# SCH_PoC_draadloze_communicatie_Jao.net
KiCad netlist of a schematic drawn in EasyEDA
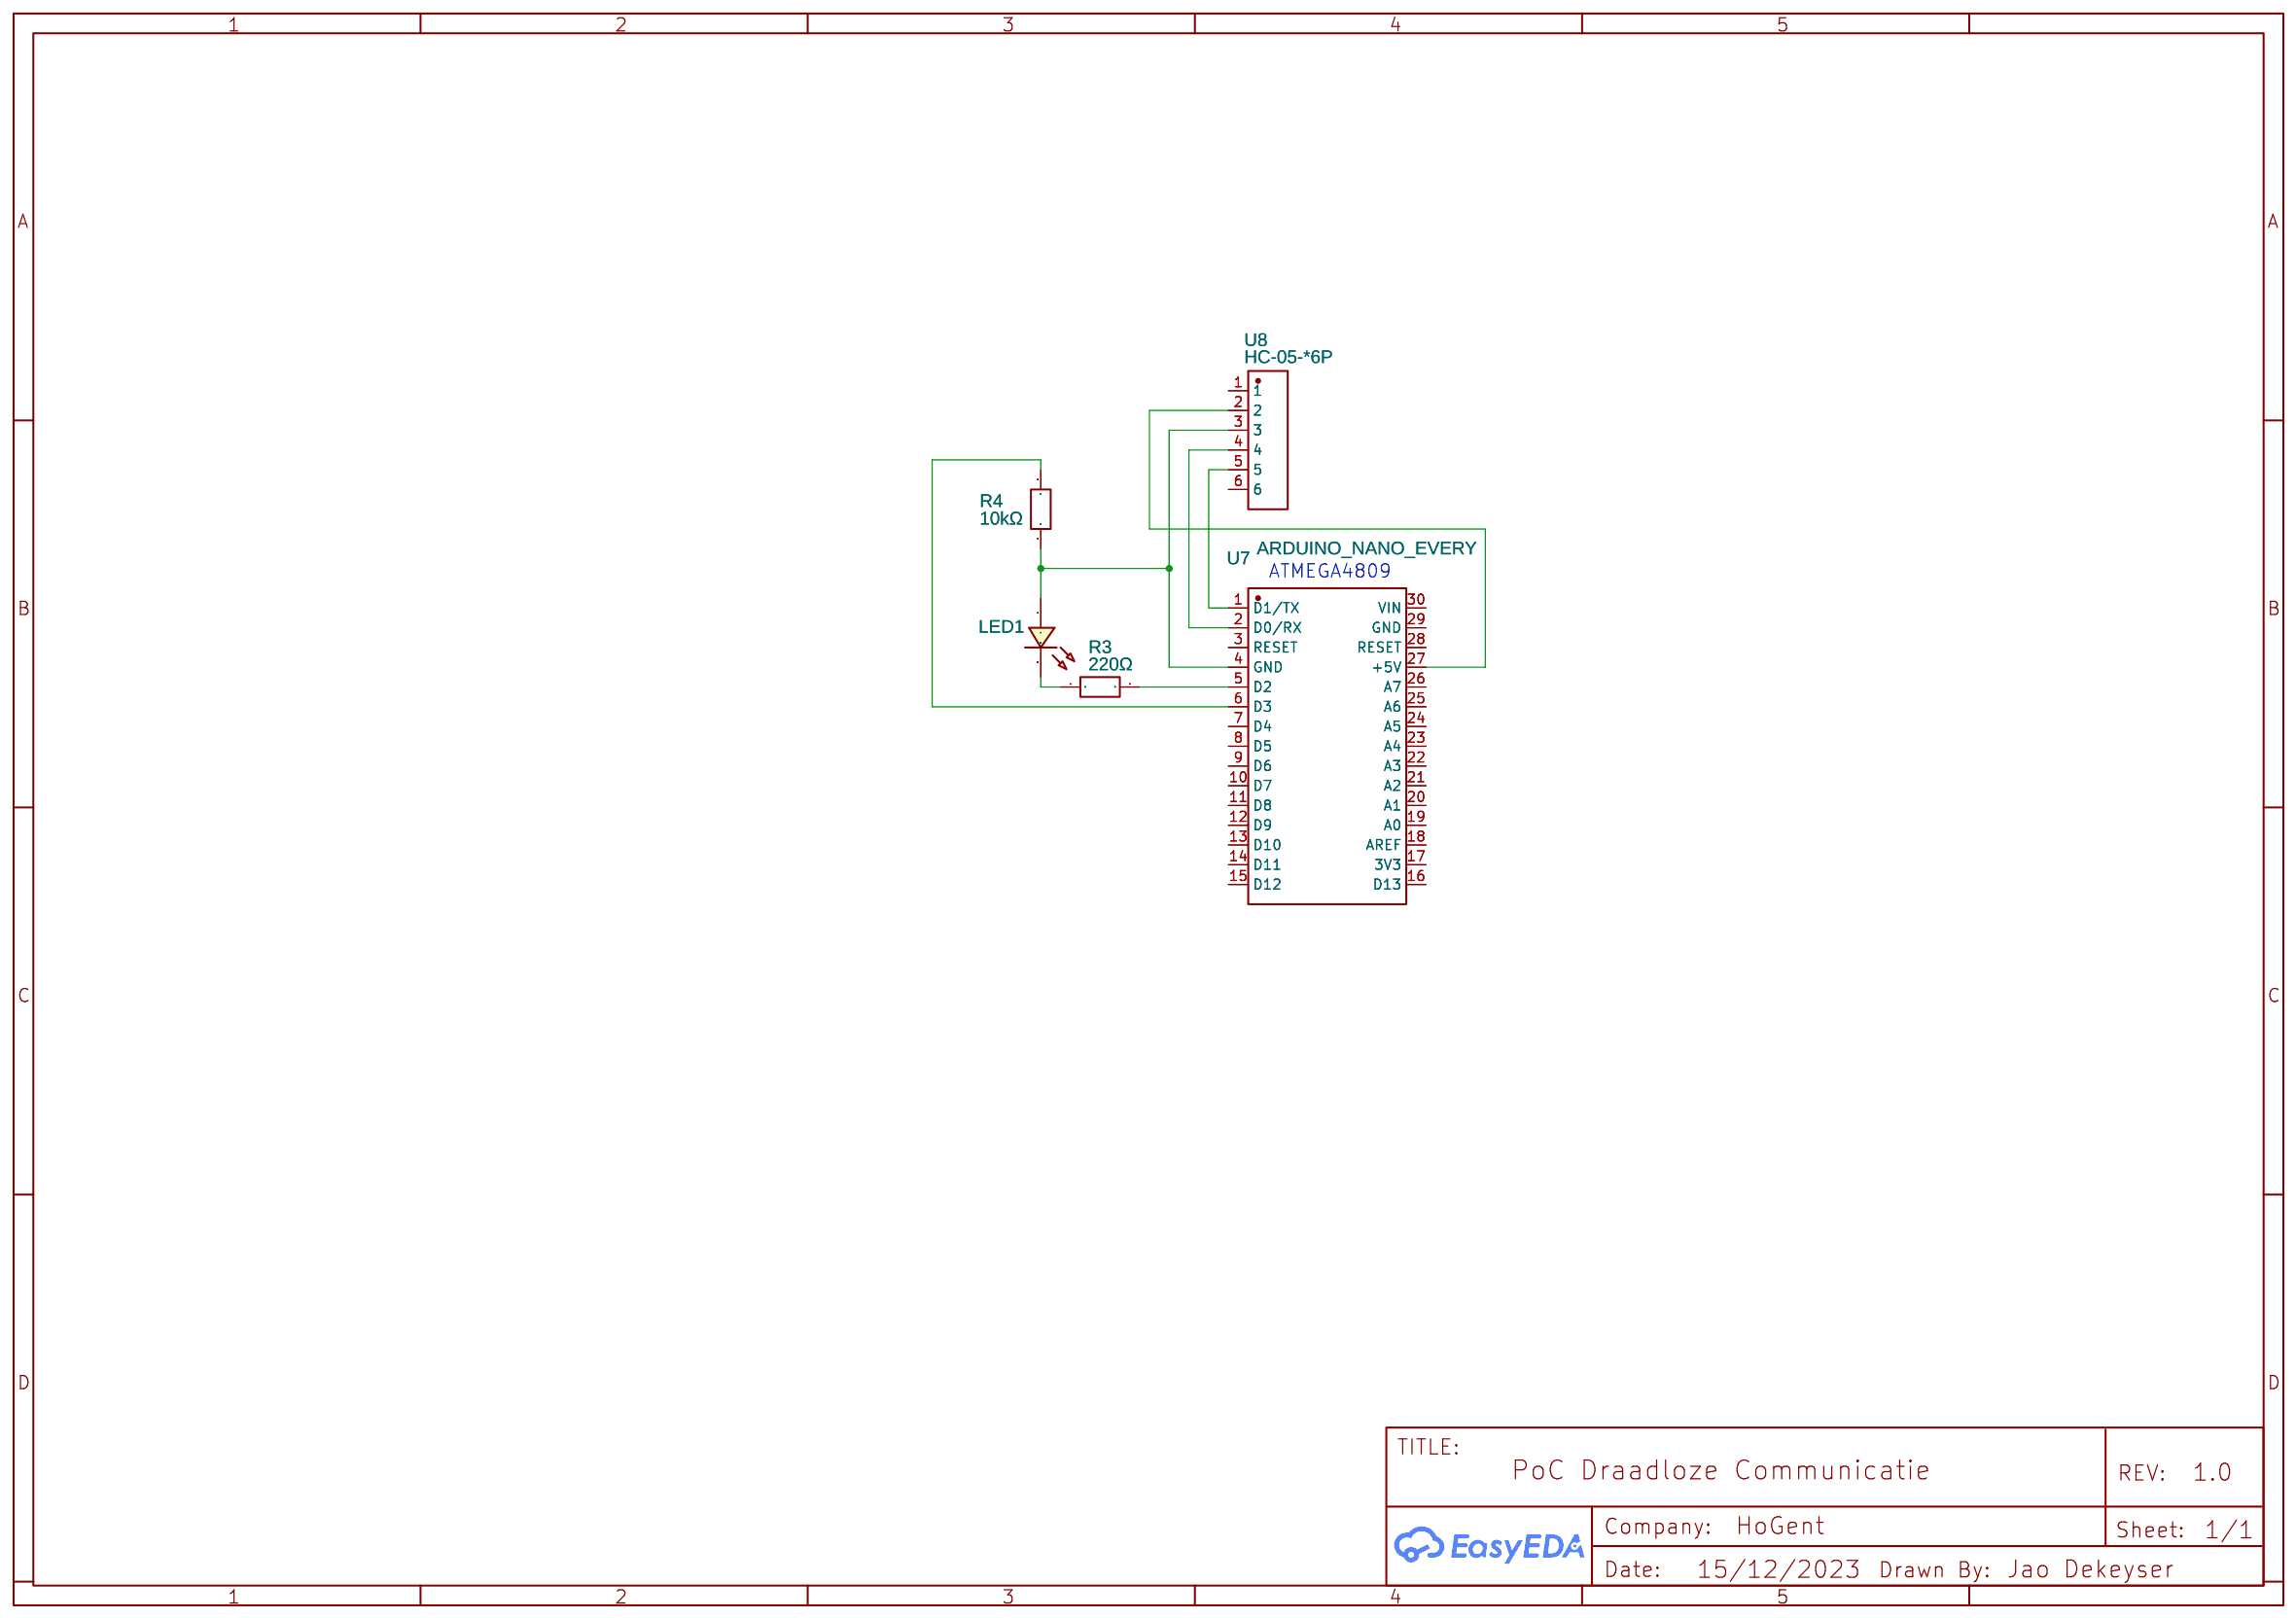
[diagram p0: schematic sheet]

(export (version "E")
  (design (tool "Eeschema 10.0.6"))
  (components
    (comp (ref "LED1")
      (value "LED-TH-5mm_R")
      (fields
        (field (name "Manufacturer Part") "333-2SURD/S530-A3")
        (field (name "Manufacturer") "EVERLIGHT(台湾亿光)")
      )
      (libsource (lib "") (part "LED-TH-5mm_R"))
    )
    (comp (ref "R3")
      (value "220Ω")
      (libsource (lib "") (part "AXIAL RESISTOR 220 OHM - TH_BD2.3-L6.0-P10.00-D0.4_1"))
    )
    (comp (ref "R4")
      (value "10kΩ")
      (libsource (lib "") (part "AXIAL RESISTOR 220 OHM - TH_BD2.3-L6.0-P10.00-D0.4"))
    )
    (comp (ref "U7")
      (value "ARDUINO_NANO_EVERY")
      (fields (field (name "Manufacturer Part") "ARDUINO_NANO"))
      (libsource (lib "") (part "ARDUINO_NANO"))
    )
    (comp (ref "U8")
      (value "HC-05-*6P")
      (fields (field (name "Manufacturer Part") "HC-05_排母*6P"))
      (libsource (lib "") (part "HC-05-*6P"))
    )
  )
  (nets
    (net (code "1") (name "Net-(LED1-Pad1)") (class "Default")
      (node (ref "LED1") (pin "1") (pinfunction "1_1") (pintype "unspecified"))
      (node (ref "R4") (pin "1") (pinfunction "1_1") (pintype "unspecified"))
      (node (ref "U7") (pin "4") (pinfunction "GND_4") (pintype "unspecified"))
      (node (ref "U8") (pin "3") (pinfunction "3_3") (pintype "unspecified"))
    )
    (net (code "2") (name "Net-(LED1-Pad2)") (class "Default")
      (node (ref "LED1") (pin "2") (pinfunction "2_2") (pintype "unspecified"))
      (node (ref "R3") (pin "1") (pinfunction "1_1") (pintype "unspecified"))
    )
    (net (code "3") (name "Net-(U7-+5V)") (class "Default")
      (node (ref "U7") (pin "27") (pinfunction "+5V_27") (pintype "unspecified"))
      (node (ref "U8") (pin "2") (pinfunction "2_2") (pintype "unspecified"))
    )
    (net (code "4") (name "Net-(U7-D0{slash}RX)") (class "Default")
      (node (ref "U7") (pin "2") (pinfunction "D0/RX_2") (pintype "unspecified"))
      (node (ref "U8") (pin "4") (pinfunction "4_4") (pintype "unspecified"))
    )
    (net (code "5") (name "Net-(U7-D1{slash}TX)") (class "Default")
      (node (ref "U7") (pin "1") (pinfunction "D1/TX_1") (pintype "unspecified"))
      (node (ref "U8") (pin "5") (pinfunction "5_5") (pintype "unspecified"))
    )
    (net (code "6") (name "Net-(U7-D2)") (class "Default")
      (node (ref "R3") (pin "2") (pinfunction "2_2") (pintype "unspecified"))
      (node (ref "U7") (pin "5") (pinfunction "D2_5") (pintype "unspecified"))
    )
    (net (code "7") (name "Net-(U7-D3)") (class "Default")
      (node (ref "R4") (pin "2") (pinfunction "2_2") (pintype "unspecified"))
      (node (ref "U7") (pin "6") (pinfunction "D3_6") (pintype "unspecified"))
    )
    (net (code "8") (name "unconnected-(U7-3V3-Pad17)") (class "Default")
      (node (ref "U7") (pin "17") (pinfunction "3V3_17") (pintype "unspecified"))
    )
    (net (code "9") (name "unconnected-(U7-A0-Pad19)") (class "Default")
      (node (ref "U7") (pin "19") (pinfunction "A0_19") (pintype "unspecified"))
    )
    (net (code "10") (name "unconnected-(U7-A1-Pad20)") (class "Default")
      (node (ref "U7") (pin "20") (pinfunction "A1_20") (pintype "unspecified"))
    )
    (net (code "11") (name "unconnected-(U7-A2-Pad21)") (class "Default")
      (node (ref "U7") (pin "21") (pinfunction "A2_21") (pintype "unspecified"))
    )
    (net (code "12") (name "unconnected-(U7-A3-Pad22)") (class "Default")
      (node (ref "U7") (pin "22") (pinfunction "A3_22") (pintype "unspecified"))
    )
    (net (code "13") (name "unconnected-(U7-A4-Pad23)") (class "Default")
      (node (ref "U7") (pin "23") (pinfunction "A4_23") (pintype "unspecified"))
    )
    (net (code "14") (name "unconnected-(U7-A5-Pad24)") (class "Default")
      (node (ref "U7") (pin "24") (pinfunction "A5_24") (pintype "unspecified"))
    )
    (net (code "15") (name "unconnected-(U7-A6-Pad25)") (class "Default")
      (node (ref "U7") (pin "25") (pinfunction "A6_25") (pintype "unspecified"))
    )
    (net (code "16") (name "unconnected-(U7-A7-Pad26)") (class "Default")
      (node (ref "U7") (pin "26") (pinfunction "A7_26") (pintype "unspecified"))
    )
    (net (code "17") (name "unconnected-(U7-AREF-Pad18)") (class "Default")
      (node (ref "U7") (pin "18") (pinfunction "AREF_18") (pintype "unspecified"))
    )
    (net (code "18") (name "unconnected-(U7-D4-Pad7)") (class "Default")
      (node (ref "U7") (pin "7") (pinfunction "D4_7") (pintype "unspecified"))
    )
    (net (code "19") (name "unconnected-(U7-D5-Pad8)") (class "Default")
      (node (ref "U7") (pin "8") (pinfunction "D5_8") (pintype "unspecified"))
    )
    (net (code "20") (name "unconnected-(U7-D6-Pad9)") (class "Default")
      (node (ref "U7") (pin "9") (pinfunction "D6_9") (pintype "unspecified"))
    )
    (net (code "21") (name "unconnected-(U7-D7-Pad10)") (class "Default")
      (node (ref "U7") (pin "10") (pinfunction "D7_10") (pintype "unspecified"))
    )
    (net (code "22") (name "unconnected-(U7-D8-Pad11)") (class "Default")
      (node (ref "U7") (pin "11") (pinfunction "D8_11") (pintype "unspecified"))
    )
    (net (code "23") (name "unconnected-(U7-D9-Pad12)") (class "Default")
      (node (ref "U7") (pin "12") (pinfunction "D9_12") (pintype "unspecified"))
    )
    (net (code "24") (name "unconnected-(U7-D10-Pad13)") (class "Default")
      (node (ref "U7") (pin "13") (pinfunction "D10_13") (pintype "unspecified"))
    )
    (net (code "25") (name "unconnected-(U7-D11-Pad14)") (class "Default")
      (node (ref "U7") (pin "14") (pinfunction "D11_14") (pintype "unspecified"))
    )
    (net (code "26") (name "unconnected-(U7-D12-Pad15)") (class "Default")
      (node (ref "U7") (pin "15") (pinfunction "D12_15") (pintype "unspecified"))
    )
    (net (code "27") (name "unconnected-(U7-D13-Pad16)") (class "Default")
      (node (ref "U7") (pin "16") (pinfunction "D13_16") (pintype "unspecified"))
    )
    (net (code "28") (name "unconnected-(U7-GND-Pad29)") (class "Default")
      (node (ref "U7") (pin "29") (pinfunction "GND_29") (pintype "unspecified"))
    )
    (net (code "29") (name "unconnected-(U7-RESET-Pad3)") (class "Default")
      (node (ref "U7") (pin "3") (pinfunction "RESET_3") (pintype "unspecified"))
    )
    (net (code "30") (name "unconnected-(U7-RESET-Pad28)") (class "Default")
      (node (ref "U7") (pin "28") (pinfunction "RESET_28") (pintype "unspecified"))
    )
    (net (code "31") (name "unconnected-(U7-VIN-Pad30)") (class "Default")
      (node (ref "U7") (pin "30") (pinfunction "VIN_30") (pintype "unspecified"))
    )
    (net (code "32") (name "unconnected-(U8-Pad1)") (class "Default")
      (node (ref "U8") (pin "1") (pinfunction "1_1") (pintype "unspecified"))
    )
    (net (code "33") (name "unconnected-(U8-Pad6)") (class "Default")
      (node (ref "U8") (pin "6") (pinfunction "6_6") (pintype "unspecified"))
    )
  )
)
